# binary_counter_down.net
KiCad netlist of a schematic drawn in EAGLE
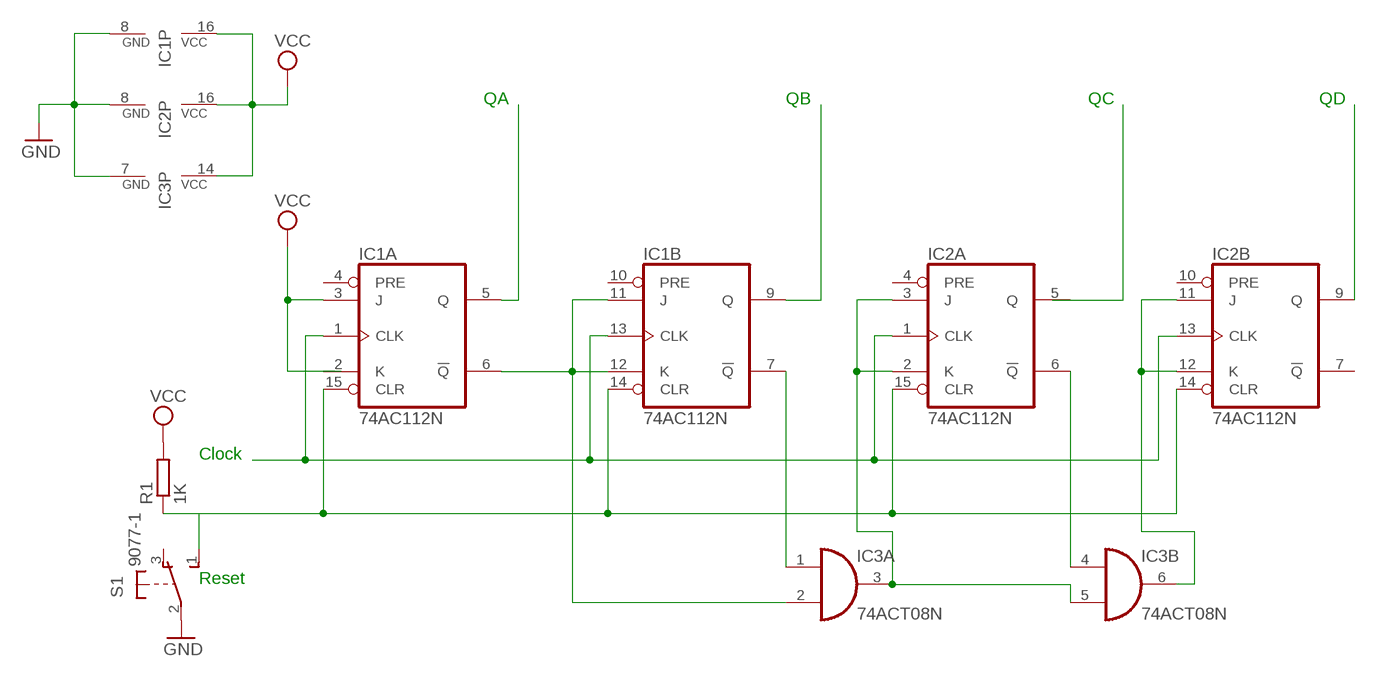
[diagram p0: schematic, sheet 1]

(export (version "E")
  (design (tool "Eeschema 10.0.6"))
  (components
    (comp (ref "IC1")
      (value "74AC112N")
      (footprint "eagle-import:DIL16")
      (libsource (lib "eagle-import") (part "74112NAC"))
    )
    (comp (ref "IC2")
      (value "74AC112N")
      (footprint "eagle-import:DIL16")
      (libsource (lib "eagle-import") (part "74112NAC"))
    )
    (comp (ref "IC3")
      (value "74ACT08N")
      (footprint "eagle-import:DIL14")
      (libsource (lib "eagle-import") (part "7408NACT"))
    )
    (comp (ref "R1")
      (value "1K")
      (footprint "eagle-import:0204_7")
      (libsource (lib "eagle-import") (part "R-EU_0204/7"))
    )
    (comp (ref "S1")
      (value "9077-1")
      (footprint "eagle-import:9077-1")
      (libsource (lib "eagle-import") (part "9077-1"))
    )
  )
  (nets
    (net (code "1") (name "GND") (class "Default")
      (node (ref "IC1") (pin "8") (pinfunction "GND_8") (pintype "power_in"))
      (node (ref "IC2") (pin "8") (pinfunction "GND_8") (pintype "power_in"))
      (node (ref "IC3") (pin "7") (pinfunction "GND_7") (pintype "power_in"))
      (node (ref "S1") (pin "2") (pinfunction "P_2") (pintype "passive"))
    )
    (net (code "2") (name "Net-(IC1A-CLK)") (class "Default")
      (node (ref "IC1") (pin "1") (pinfunction "CLK_1") (pintype "input"))
      (node (ref "IC1") (pin "13") (pinfunction "CLK_13") (pintype "input"))
      (node (ref "IC2") (pin "1") (pinfunction "CLK_1") (pintype "input"))
      (node (ref "IC2") (pin "13") (pinfunction "CLK_13") (pintype "input"))
    )
    (net (code "3") (name "Net-(IC1A-CLR)") (class "Default")
      (node (ref "IC1") (pin "14") (pinfunction "CLR_14") (pintype "input"))
      (node (ref "IC1") (pin "15") (pinfunction "CLR_15") (pintype "input"))
      (node (ref "IC2") (pin "14") (pinfunction "CLR_14") (pintype "input"))
      (node (ref "IC2") (pin "15") (pinfunction "CLR_15") (pintype "input"))
      (node (ref "R1") (pin "1") (pinfunction "1_1") (pintype "passive"))
      (node (ref "S1") (pin "1") (pinfunction "S_1") (pintype "passive"))
    )
    (net (code "4") (name "Net-(IC1A-~{Q})") (class "Default")
      (node (ref "IC1") (pin "11") (pinfunction "J_11") (pintype "input"))
      (node (ref "IC1") (pin "12") (pinfunction "K_12") (pintype "input"))
      (node (ref "IC1") (pin "6") (pinfunction "~{Q}_6") (pintype "output"))
      (node (ref "IC3") (pin "2") (pinfunction "I1_2") (pintype "input"))
    )
    (net (code "5") (name "Net-(IC1B-~{Q})") (class "Default")
      (node (ref "IC1") (pin "7") (pinfunction "~{Q}_7") (pintype "output"))
      (node (ref "IC3") (pin "1") (pinfunction "I0_1") (pintype "input"))
    )
    (net (code "6") (name "Net-(IC2A-J)") (class "Default")
      (node (ref "IC2") (pin "2") (pinfunction "K_2") (pintype "input"))
      (node (ref "IC2") (pin "3") (pinfunction "J_3") (pintype "input"))
      (node (ref "IC3") (pin "3") (pinfunction "O_3") (pintype "output"))
      (node (ref "IC3") (pin "5") (pinfunction "I1_5") (pintype "input"))
    )
    (net (code "7") (name "Net-(IC2A-~{Q})") (class "Default")
      (node (ref "IC2") (pin "6") (pinfunction "~{Q}_6") (pintype "output"))
      (node (ref "IC3") (pin "4") (pinfunction "I0_4") (pintype "input"))
    )
    (net (code "8") (name "Net-(IC2B-J)") (class "Default")
      (node (ref "IC2") (pin "11") (pinfunction "J_11") (pintype "input"))
      (node (ref "IC2") (pin "12") (pinfunction "K_12") (pintype "input"))
      (node (ref "IC3") (pin "6") (pinfunction "O_6") (pintype "output"))
    )
    (net (code "9") (name "VCC") (class "Default")
      (node (ref "IC1") (pin "16") (pinfunction "VCC_16") (pintype "power_in"))
      (node (ref "IC1") (pin "3") (pinfunction "J_3") (pintype "input"))
      (node (ref "IC2") (pin "16") (pinfunction "VCC_16") (pintype "power_in"))
      (node (ref "IC3") (pin "14") (pinfunction "VCC_14") (pintype "power_in"))
      (node (ref "R1") (pin "2") (pinfunction "2_2") (pintype "passive"))
    )
    (net (code "10") (name "unconnected-(IC1A-K-Pad2)") (class "Default")
      (node (ref "IC1") (pin "2") (pinfunction "K_2") (pintype "input"))
    )
    (net (code "11") (name "unconnected-(IC1A-PRE-Pad4)") (class "Default")
      (node (ref "IC1") (pin "4") (pinfunction "PRE_4") (pintype "input"))
    )
    (net (code "12") (name "unconnected-(IC1A-Q-Pad5)") (class "Default")
      (node (ref "IC1") (pin "5") (pinfunction "Q_5") (pintype "output"))
    )
    (net (code "13") (name "unconnected-(IC1B-PRE-Pad10)") (class "Default")
      (node (ref "IC1") (pin "10") (pinfunction "PRE_10") (pintype "input"))
    )
    (net (code "14") (name "unconnected-(IC1B-Q-Pad9)") (class "Default")
      (node (ref "IC1") (pin "9") (pinfunction "Q_9") (pintype "output"))
    )
    (net (code "15") (name "unconnected-(IC2A-PRE-Pad4)") (class "Default")
      (node (ref "IC2") (pin "4") (pinfunction "PRE_4") (pintype "input"))
    )
    (net (code "16") (name "unconnected-(IC2A-Q-Pad5)") (class "Default")
      (node (ref "IC2") (pin "5") (pinfunction "Q_5") (pintype "output"))
    )
    (net (code "17") (name "unconnected-(IC2B-PRE-Pad10)") (class "Default")
      (node (ref "IC2") (pin "10") (pinfunction "PRE_10") (pintype "input"))
    )
    (net (code "18") (name "unconnected-(IC2B-Q-Pad9)") (class "Default")
      (node (ref "IC2") (pin "9") (pinfunction "Q_9") (pintype "output"))
    )
    (net (code "19") (name "unconnected-(IC2B-~{Q}-Pad7)") (class "Default")
      (node (ref "IC2") (pin "7") (pinfunction "~{Q}_7") (pintype "output"))
    )
    (net (code "20") (name "unconnected-(S1-O-Pad3)") (class "Default")
      (node (ref "S1") (pin "3") (pinfunction "O_3") (pintype "passive"))
    )
  )
)
